# sharp_breakout_v1.net
KiCad netlist of a schematic drawn in EAGLE
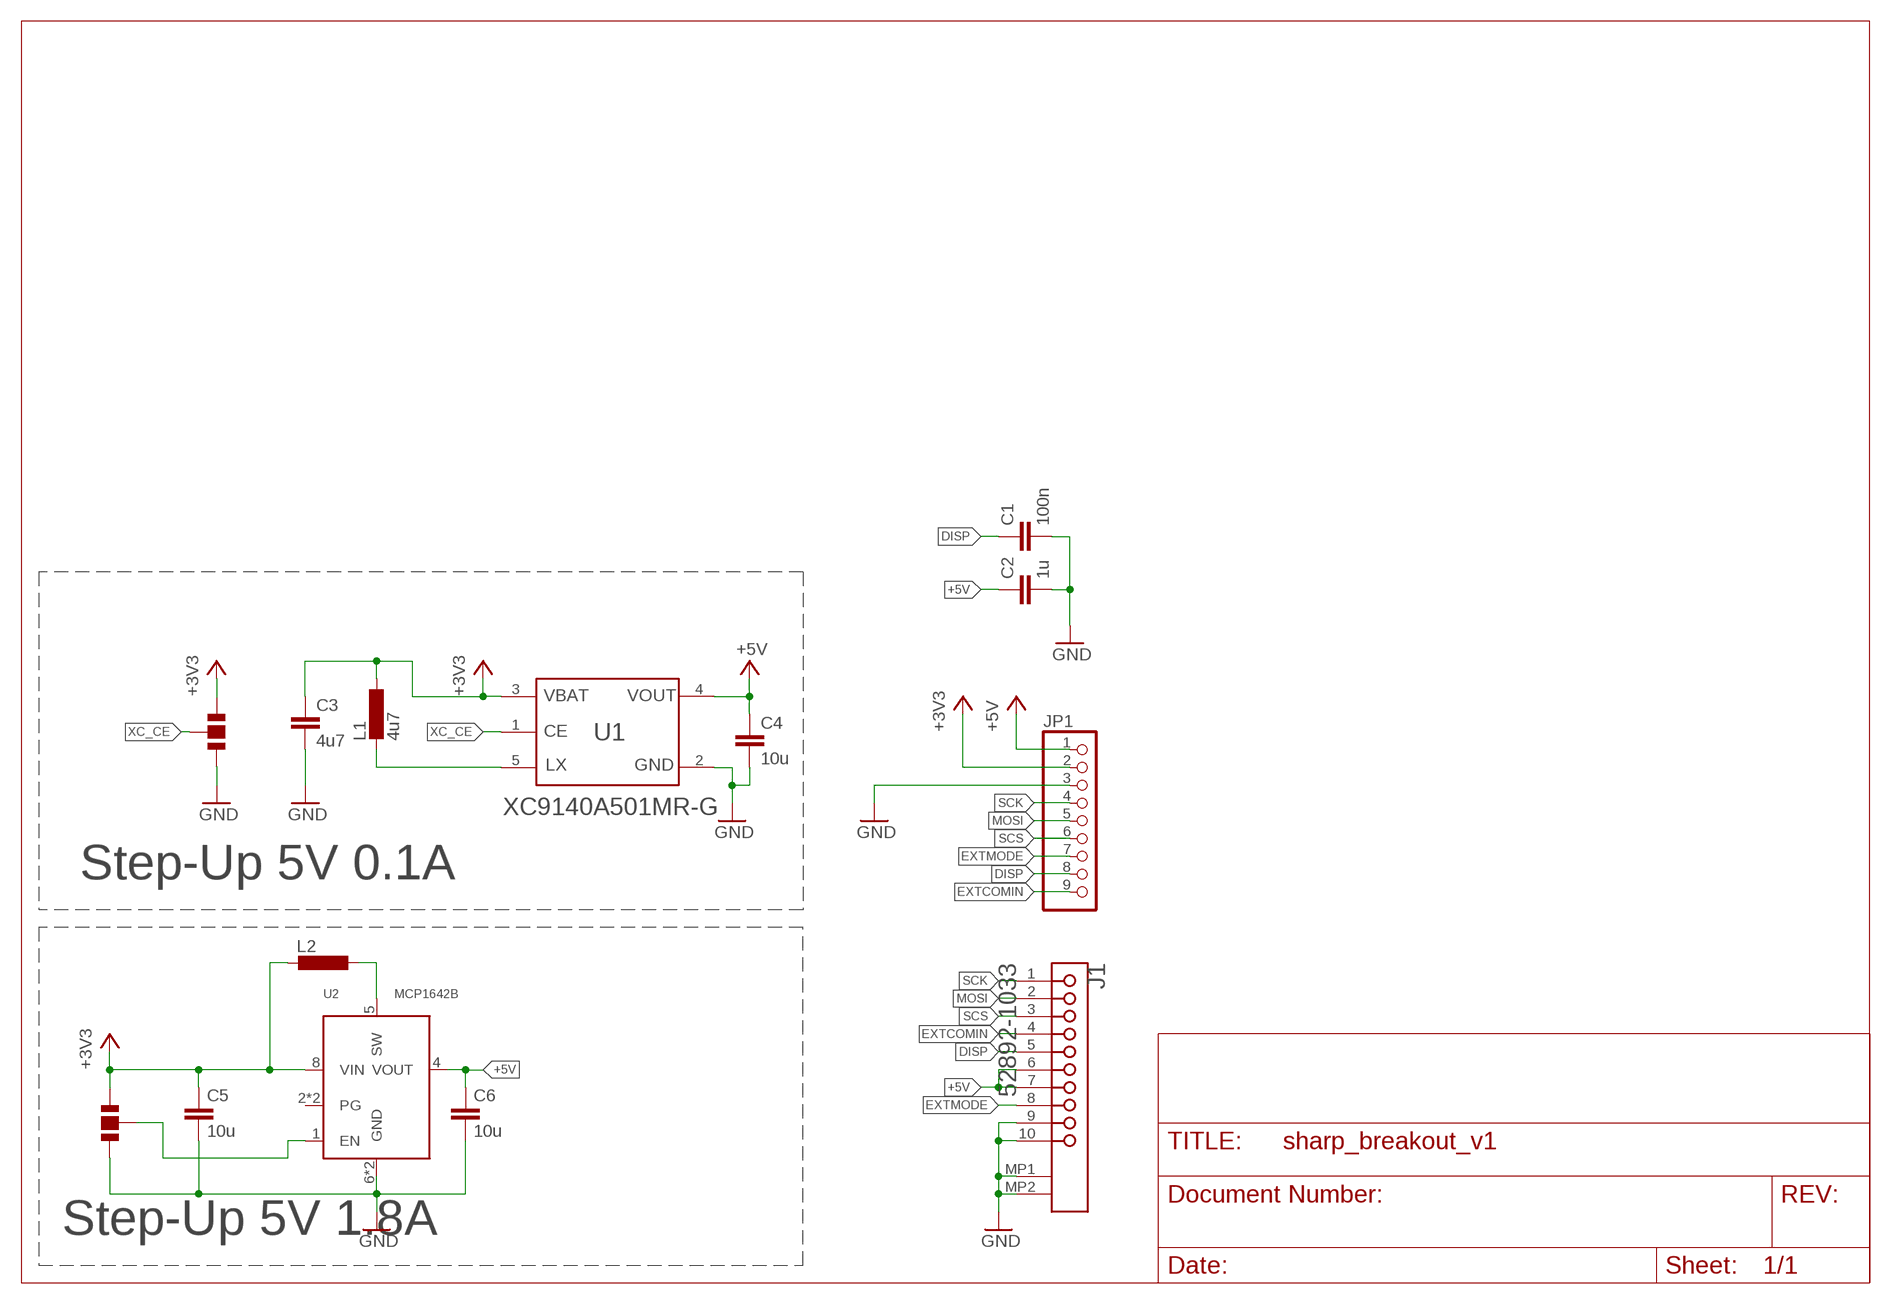
[diagram p0: schematic, sheet 1]

(export (version "E")
  (design (tool "Eeschema 10.0.6"))
  (components
    (comp (ref "C1")
      (value "100n")
      (footprint "eagle-import:C0603K")
      (libsource (lib "eagle-import") (part "C-EUC0603K"))
    )
    (comp (ref "C2")
      (value "1u")
      (footprint "eagle-import:C0603K")
      (libsource (lib "eagle-import") (part "C-EUC0603K"))
    )
    (comp (ref "C3")
      (value "4u7")
      (footprint "eagle-import:C0603K")
      (libsource (lib "eagle-import") (part "C-EUC0603K"))
    )
    (comp (ref "C4")
      (value "10u")
      (footprint "eagle-import:C0603K")
      (libsource (lib "eagle-import") (part "C-EUC0603K"))
    )
    (comp (ref "C5")
      (value "10u")
      (footprint "eagle-import:C1206")
      (libsource (lib "eagle-import") (part "C-EUC1206"))
    )
    (comp (ref "C6")
      (value "10u")
      (footprint "eagle-import:C1206")
      (libsource (lib "eagle-import") (part "C-EUC1206"))
    )
    (comp (ref "J1")
      (value "MOLEX_52892-1033MOLEX_52892-1033_0_0")
      (footprint "eagle-import:MOLEX_52892-1033_0")
      (fields (field (name "MF") "Molex") (field (name "MPN") "52892-1033"))
      (libsource (lib "eagle-import") (part "MOLEX_52892-1033MOLEX_52892-1033_0_0"))
    )
    (comp (ref "JP1")
      (value "PINHD-1X9")
      (footprint "eagle-import:1X09")
      (libsource (lib "eagle-import") (part "PINHD-1X9"))
    )
    (comp (ref "L1")
      (value "4u7")
      (footprint "eagle-import:L3225M")
      (libsource (lib "eagle-import") (part "L-EUL3225M"))
    )
    (comp (ref "L2")
      (value "L-EUL4532P")
      (footprint "eagle-import:L4532P")
      (libsource (lib "eagle-import") (part "L-EUL4532P"))
    )
    (comp (ref "U$1")
      (value "JUMPER")
      (footprint "eagle-import:2-WAY")
      (libsource (lib "eagle-import") (part "JUMPER"))
    )
    (comp (ref "U$7")
      (value "JUMPER")
      (footprint "eagle-import:2-WAY")
      (libsource (lib "eagle-import") (part "JUMPER"))
    )
    (comp (ref "U1")
      (value "TOREX_XC9140A501MR-GTOREX_XC9140A501MR-G_0_0")
      (footprint "eagle-import:TOREX_XC9140A501MR-G_0")
      (fields
        (field (name "DIGIKEY_PART_NUMBER") "893-1181-1-ND")
        (field (name "MF") "Torex")
        (field (name "MOUSER_PART_NUMBER") "865-XC9140A501MR-G")
      )
      (libsource (lib "eagle-import") (part "TOREX_XC9140A501MR-GTOREX_XC9140A501MR-G_0_0"))
    )
    (comp (ref "U2")
      (value "MCP1642B")
      (footprint "eagle-import:MSOP8")
      (libsource (lib "eagle-import") (part "MCP1642B"))
    )
  )
  (nets
    (net (code "1") (name "+3V3") (class "Default")
      (node (ref "C3") (pin "1") (pinfunction "1_1") (pintype "passive"))
      (node (ref "C5") (pin "1") (pinfunction "1_1") (pintype "passive"))
      (node (ref "JP1") (pin "2") (pinfunction "2_2") (pintype "passive"))
      (node (ref "L1") (pin "1") (pinfunction "1_1") (pintype "passive"))
      (node (ref "L2") (pin "2") (pinfunction "2_2") (pintype "passive"))
      (node (ref "U$1") (pin "P$3") (pinfunction "P$3_P$3") (pintype "bidirectional"))
      (node (ref "U$7") (pin "P$2") (pinfunction "P$2_P$2") (pintype "bidirectional"))
      (node (ref "U1") (pin "3") (pinfunction "VBAT_3") (pintype "input"))
      (node (ref "U2") (pin "8") (pinfunction "VIN_8") (pintype "power_in"))
    )
    (net (code "2") (name "+5V") (class "Default")
      (node (ref "C2") (pin "1") (pinfunction "1_1") (pintype "passive"))
      (node (ref "C4") (pin "1") (pinfunction "1_1") (pintype "passive"))
      (node (ref "C6") (pin "1") (pinfunction "1_1") (pintype "passive"))
      (node (ref "J1") (pin "6") (pinfunction "6_6") (pintype "passive"))
      (node (ref "J1") (pin "7") (pinfunction "7_7") (pintype "passive"))
      (node (ref "JP1") (pin "1") (pinfunction "1_1") (pintype "passive"))
      (node (ref "U1") (pin "4") (pinfunction "VOUT_4") (pintype "output"))
      (node (ref "U2") (pin "4") (pinfunction "VOUT_4") (pintype "power_in"))
    )
    (net (code "3") (name "DISP") (class "Default")
      (node (ref "C1") (pin "1") (pinfunction "1_1") (pintype "passive"))
      (node (ref "J1") (pin "5") (pinfunction "5_5") (pintype "passive"))
      (node (ref "JP1") (pin "8") (pinfunction "8_8") (pintype "passive"))
    )
    (net (code "4") (name "EXTCOMIN") (class "Default")
      (node (ref "J1") (pin "4") (pinfunction "4_4") (pintype "passive"))
      (node (ref "JP1") (pin "9") (pinfunction "9_9") (pintype "passive"))
    )
    (net (code "5") (name "EXTMODE") (class "Default")
      (node (ref "J1") (pin "8") (pinfunction "8_8") (pintype "passive"))
      (node (ref "JP1") (pin "7") (pinfunction "7_7") (pintype "passive"))
    )
    (net (code "6") (name "GND") (class "Default")
      (node (ref "C1") (pin "2") (pinfunction "2_2") (pintype "passive"))
      (node (ref "C2") (pin "2") (pinfunction "2_2") (pintype "passive"))
      (node (ref "C3") (pin "2") (pinfunction "2_2") (pintype "passive"))
      (node (ref "C4") (pin "2") (pinfunction "2_2") (pintype "passive"))
      (node (ref "C5") (pin "2") (pinfunction "2_2") (pintype "passive"))
      (node (ref "C6") (pin "2") (pinfunction "2_2") (pintype "passive"))
      (node (ref "J1") (pin "10") (pinfunction "10_10") (pintype "passive"))
      (node (ref "J1") (pin "9") (pinfunction "9_9") (pintype "passive"))
      (node (ref "J1") (pin "MP1") (pinfunction "MP1_MP1") (pintype "passive"))
      (node (ref "J1") (pin "MP2") (pinfunction "MP2_MP2") (pintype "passive"))
      (node (ref "JP1") (pin "3") (pinfunction "3_3") (pintype "passive"))
      (node (ref "U$1") (pin "P$2") (pinfunction "P$2_P$2") (pintype "bidirectional"))
      (node (ref "U$7") (pin "P$3") (pinfunction "P$3_P$3") (pintype "bidirectional"))
      (node (ref "U1") (pin "2") (pinfunction "GND_2") (pintype "power_in"))
      (node (ref "U2") (pin "6") (pinfunction "GND_6") (pintype "power_in"))
      (node (ref "U2") (pin "7") (pinfunction "GND_7") (pintype "power_in"))
    )
    (net (code "7") (name "MOSI") (class "Default")
      (node (ref "J1") (pin "2") (pinfunction "2_2") (pintype "passive"))
      (node (ref "JP1") (pin "5") (pinfunction "5_5") (pintype "passive"))
    )
    (net (code "8") (name "Net-(U1-LX)") (class "Default")
      (node (ref "L1") (pin "2") (pinfunction "2_2") (pintype "passive"))
      (node (ref "U1") (pin "5") (pinfunction "LX_5") (pintype "passive"))
    )
    (net (code "9") (name "Net-(U2-EN)") (class "Default")
      (node (ref "U$7") (pin "P$1") (pinfunction "P$1_P$1") (pintype "bidirectional"))
      (node (ref "U2") (pin "1") (pinfunction "EN_1") (pintype "input"))
    )
    (net (code "10") (name "Net-(U2-SW)") (class "Default")
      (node (ref "L2") (pin "1") (pinfunction "1_1") (pintype "passive"))
      (node (ref "U2") (pin "5") (pinfunction "SW_5") (pintype "power_in"))
    )
    (net (code "11") (name "SCK") (class "Default")
      (node (ref "J1") (pin "1") (pinfunction "1_1") (pintype "passive"))
      (node (ref "JP1") (pin "4") (pinfunction "4_4") (pintype "passive"))
    )
    (net (code "12") (name "SCS") (class "Default")
      (node (ref "J1") (pin "3") (pinfunction "3_3") (pintype "passive"))
      (node (ref "JP1") (pin "6") (pinfunction "6_6") (pintype "passive"))
    )
    (net (code "13") (name "XC_CE") (class "Default")
      (node (ref "U$1") (pin "P$1") (pinfunction "P$1_P$1") (pintype "bidirectional"))
      (node (ref "U1") (pin "1") (pinfunction "CE_1") (pintype "passive"))
    )
    (net (code "14") (name "unconnected-(U2-PG-Pad2)") (class "Default")
      (node (ref "U2") (pin "2") (pinfunction "PG_2") (pintype "no_connect"))
    )
    (net (code "15") (name "unconnected-(U2-PG-Pad3)") (class "Default")
      (node (ref "U2") (pin "3") (pinfunction "PG_3") (pintype "no_connect"))
    )
  )
)
